# mezza.net
KiCad netlist of a schematic drawn in EAGLE
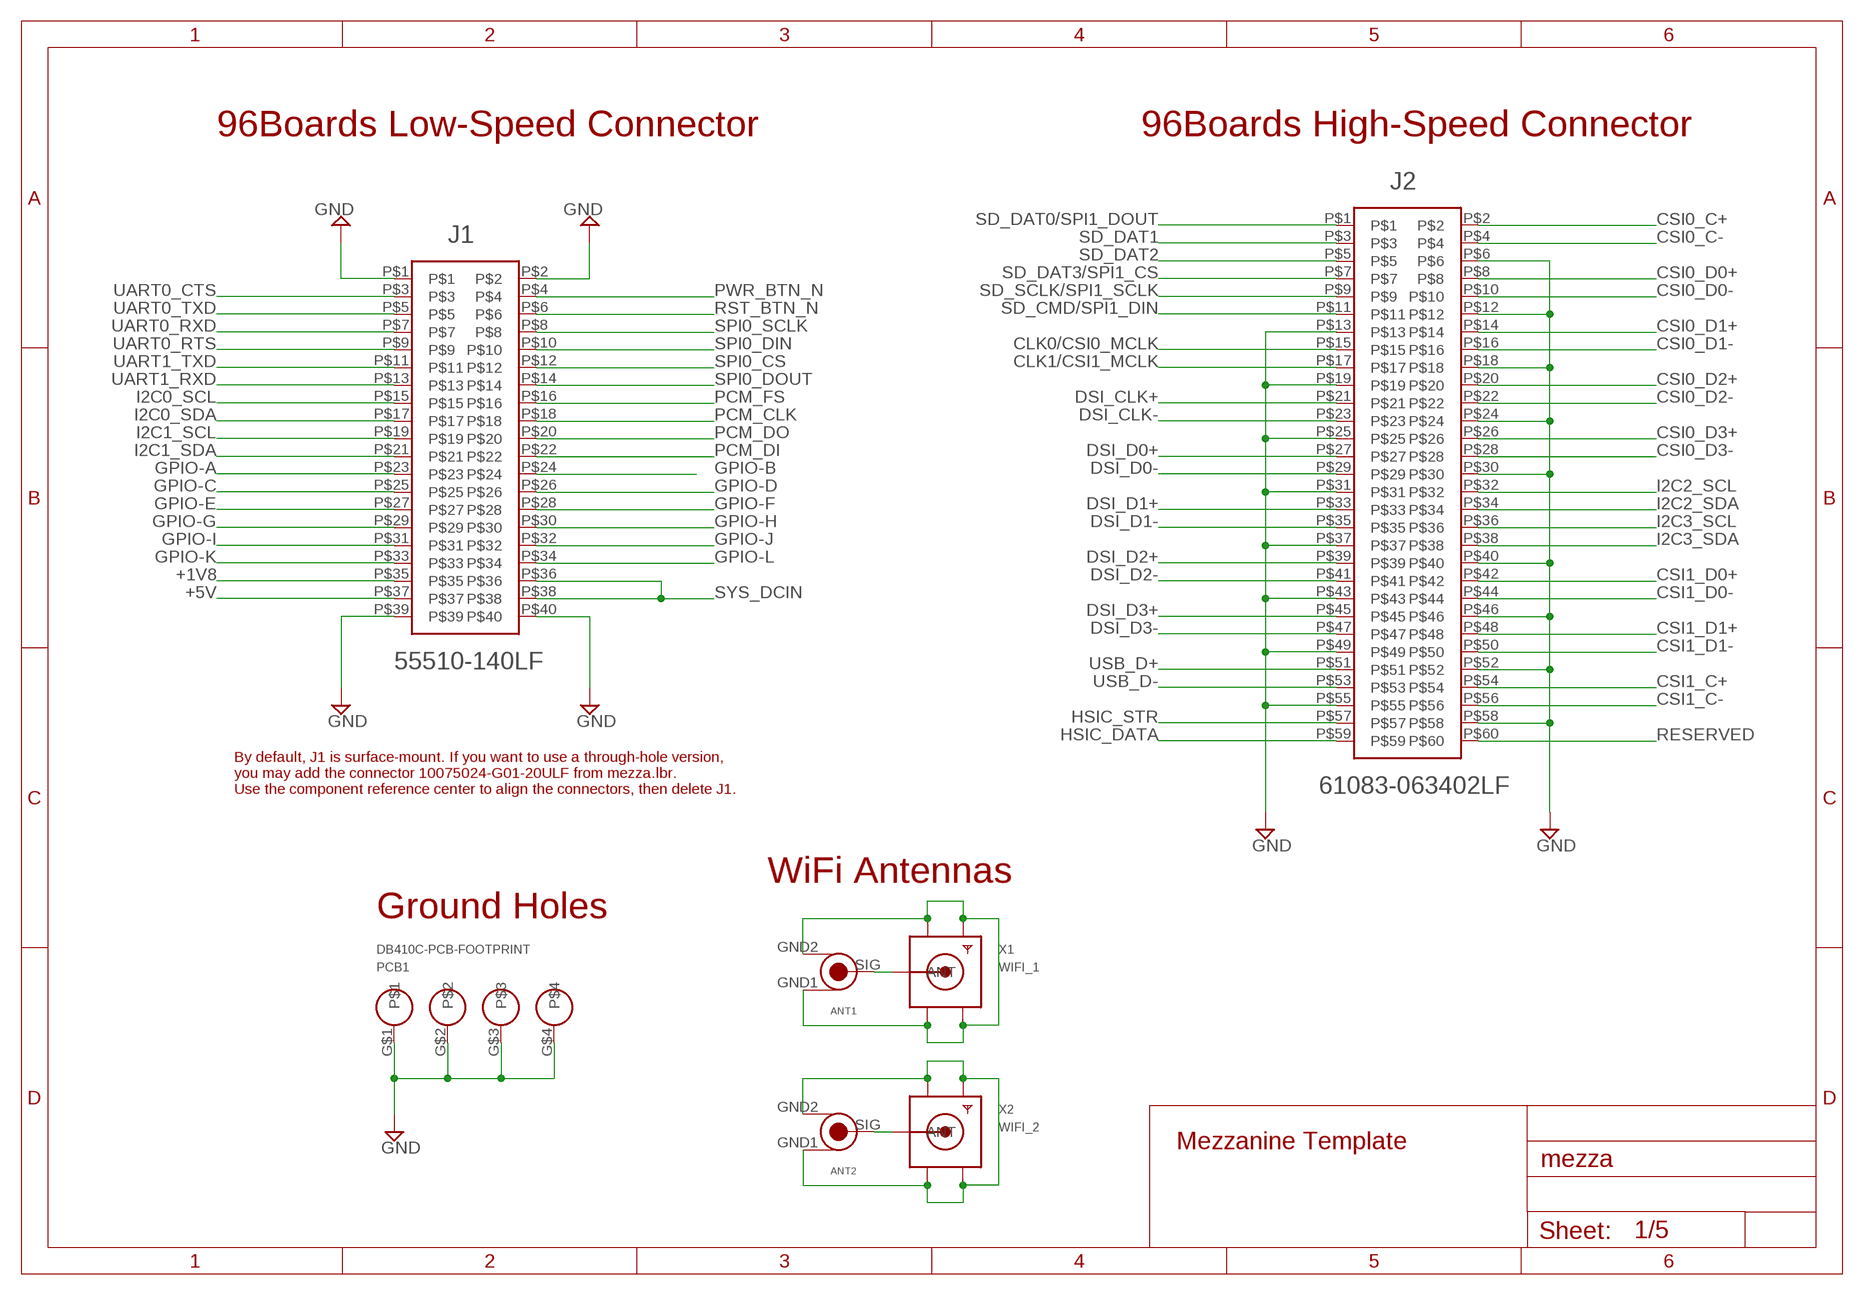
[diagram p0: schematic, sheet 1]
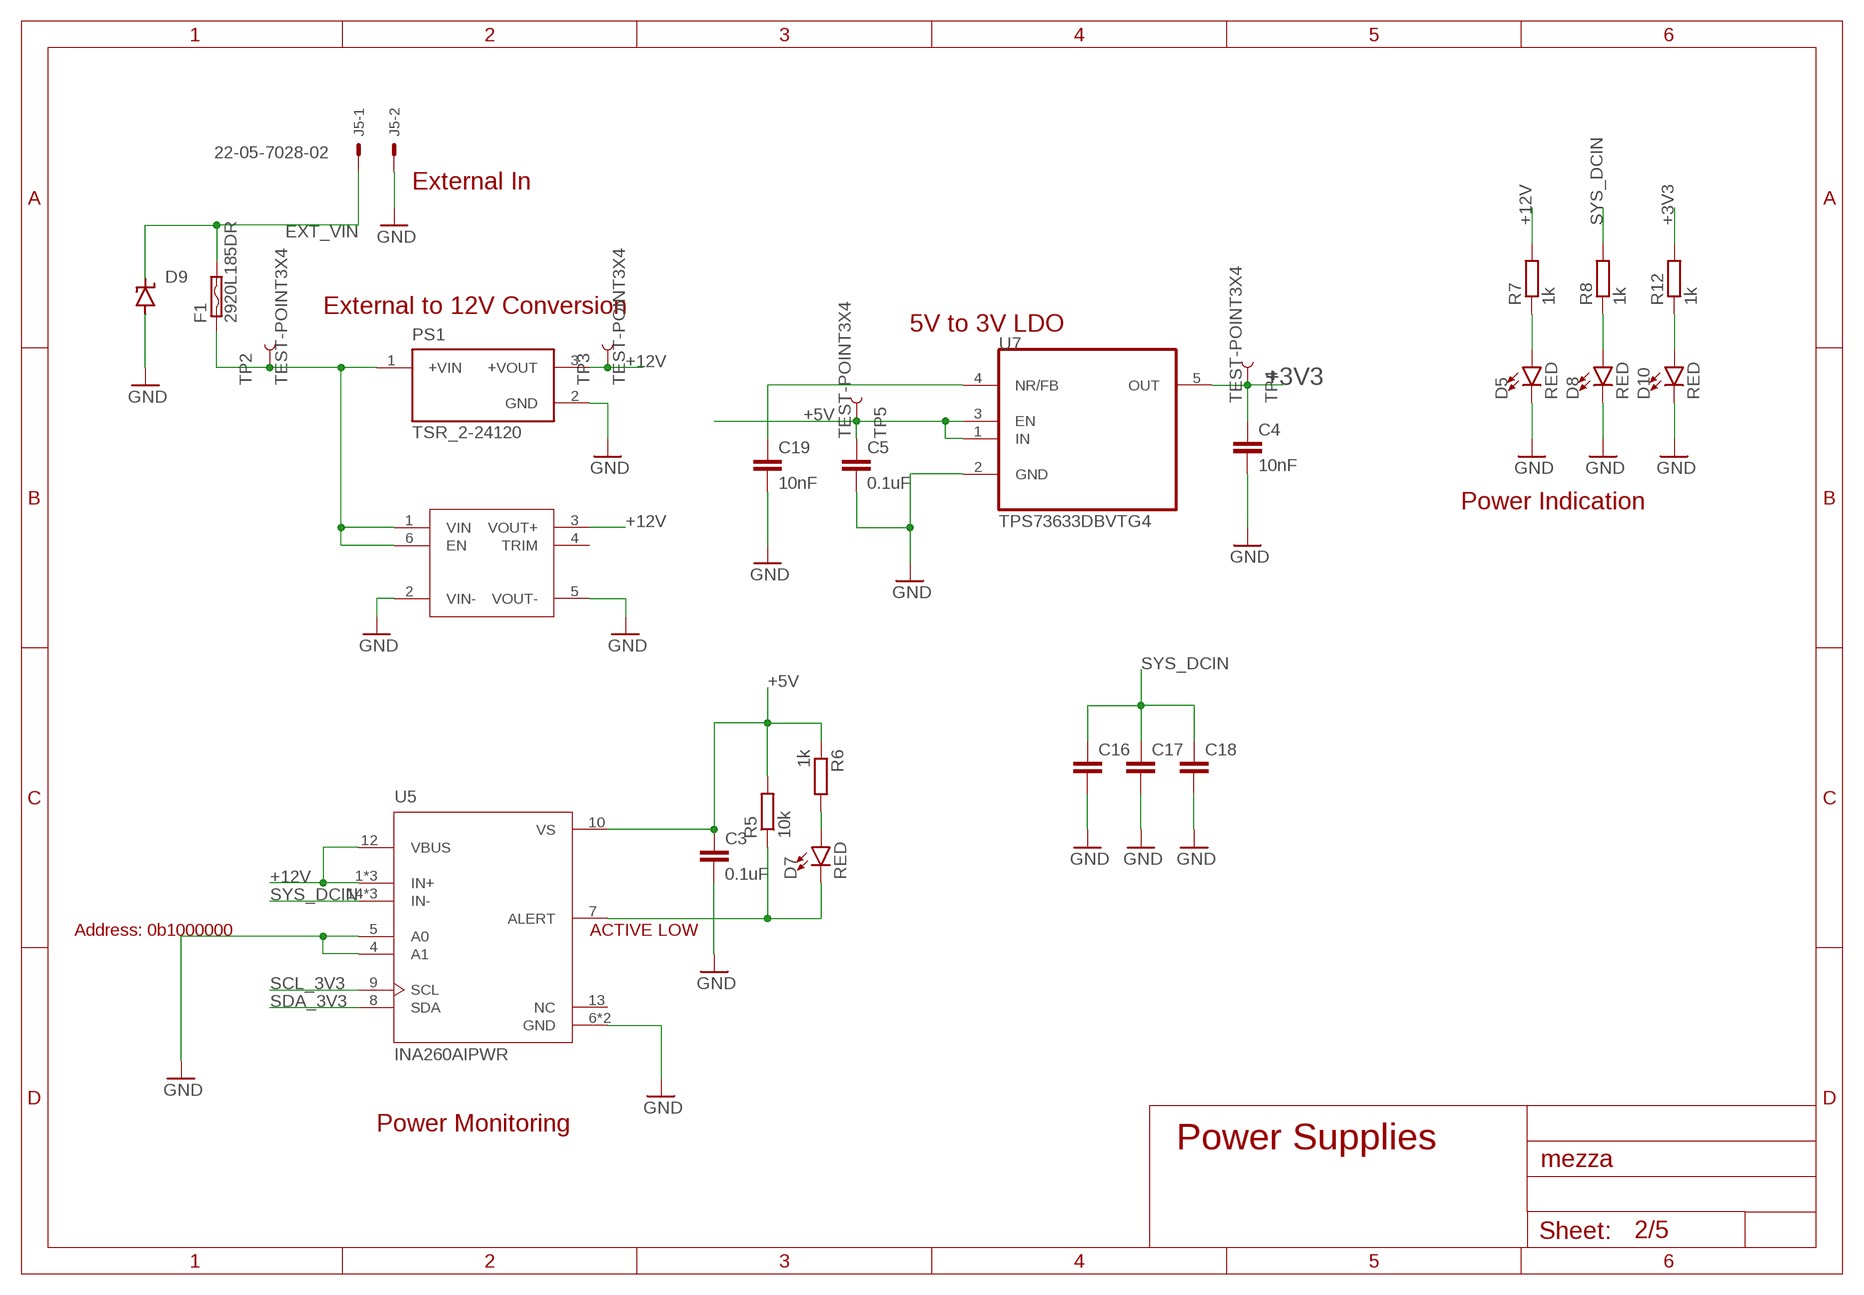
[diagram p1: schematic, sheet 2]
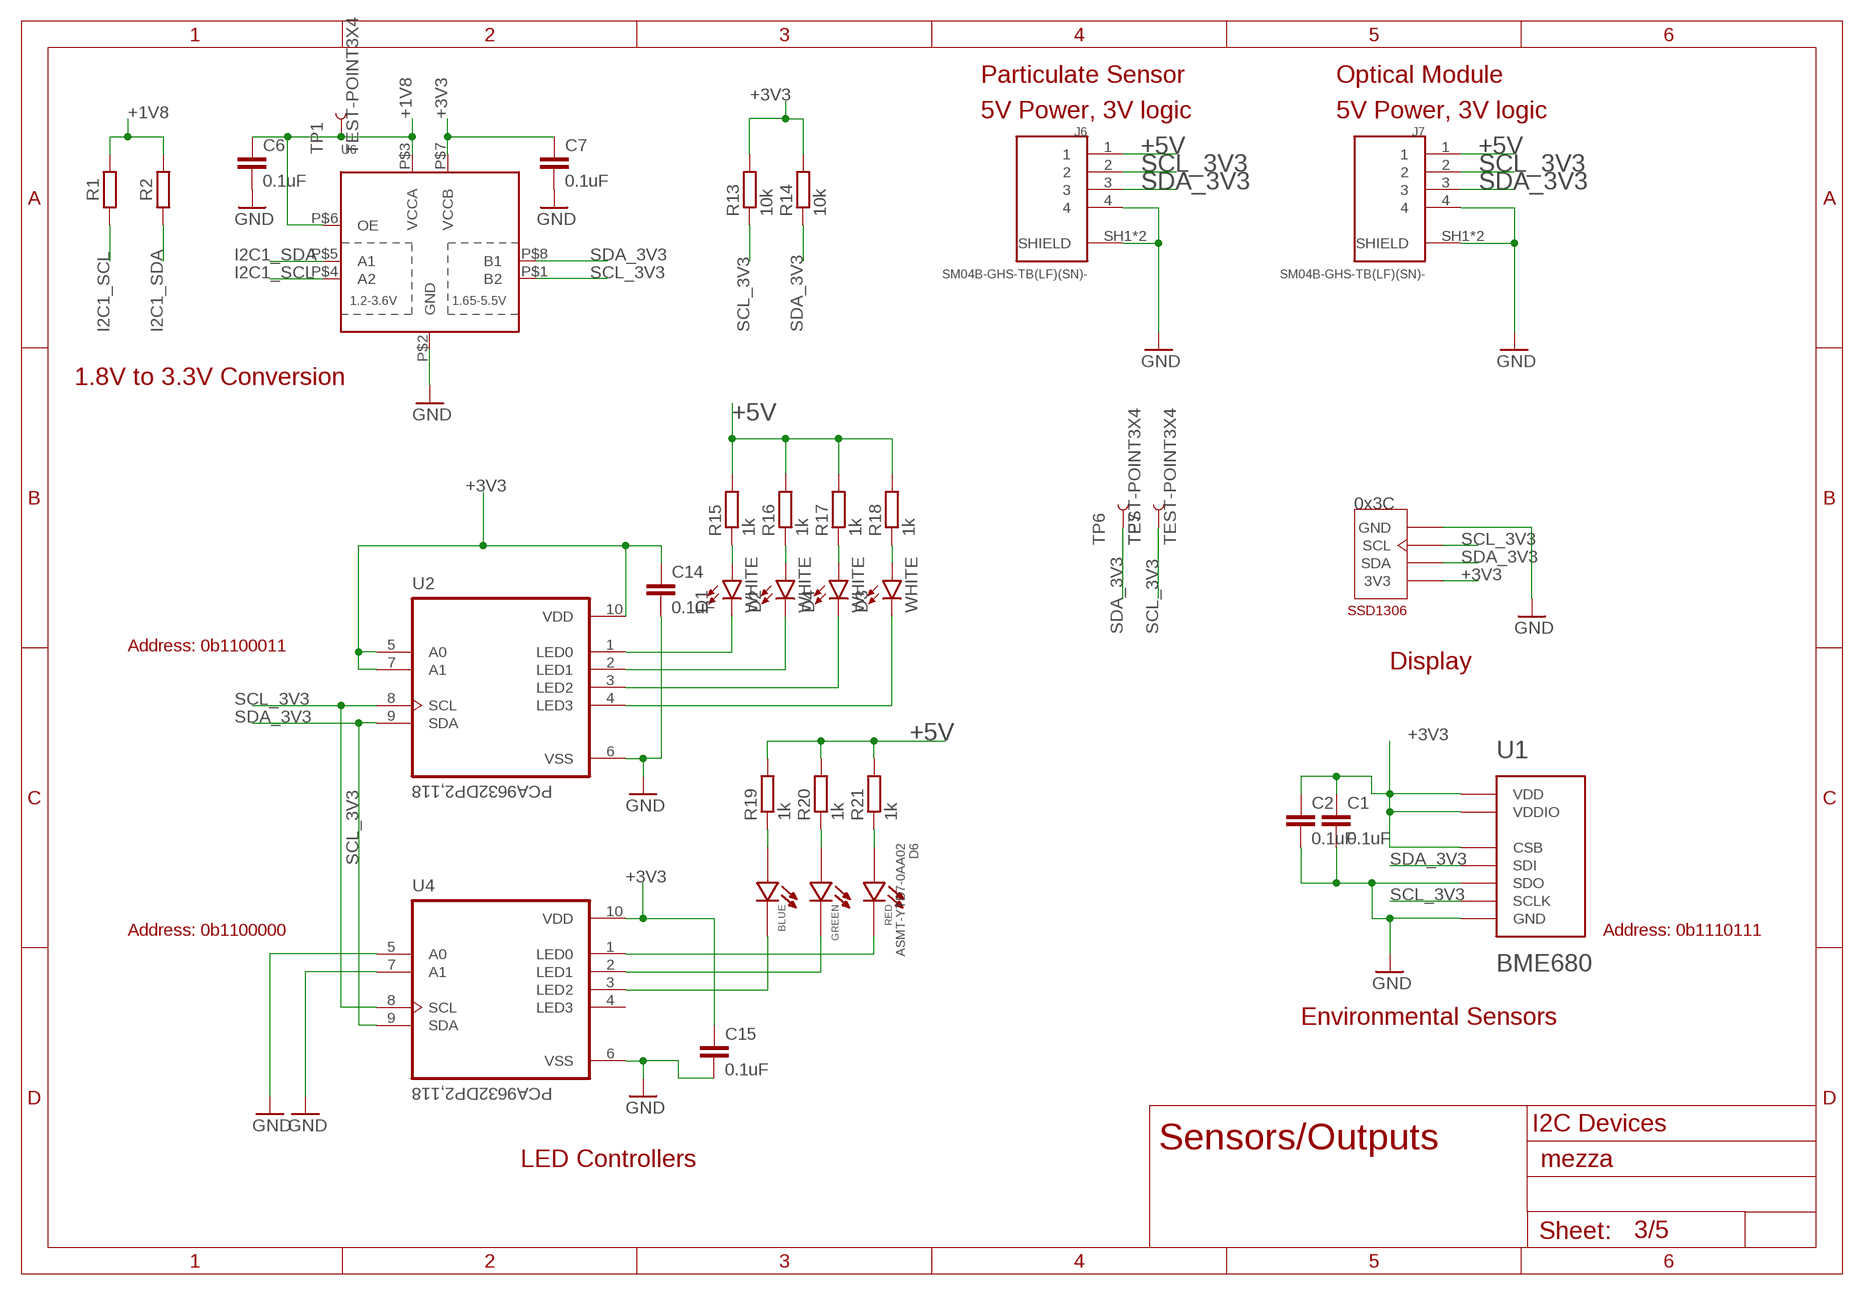
[diagram p2: schematic, sheet 3]
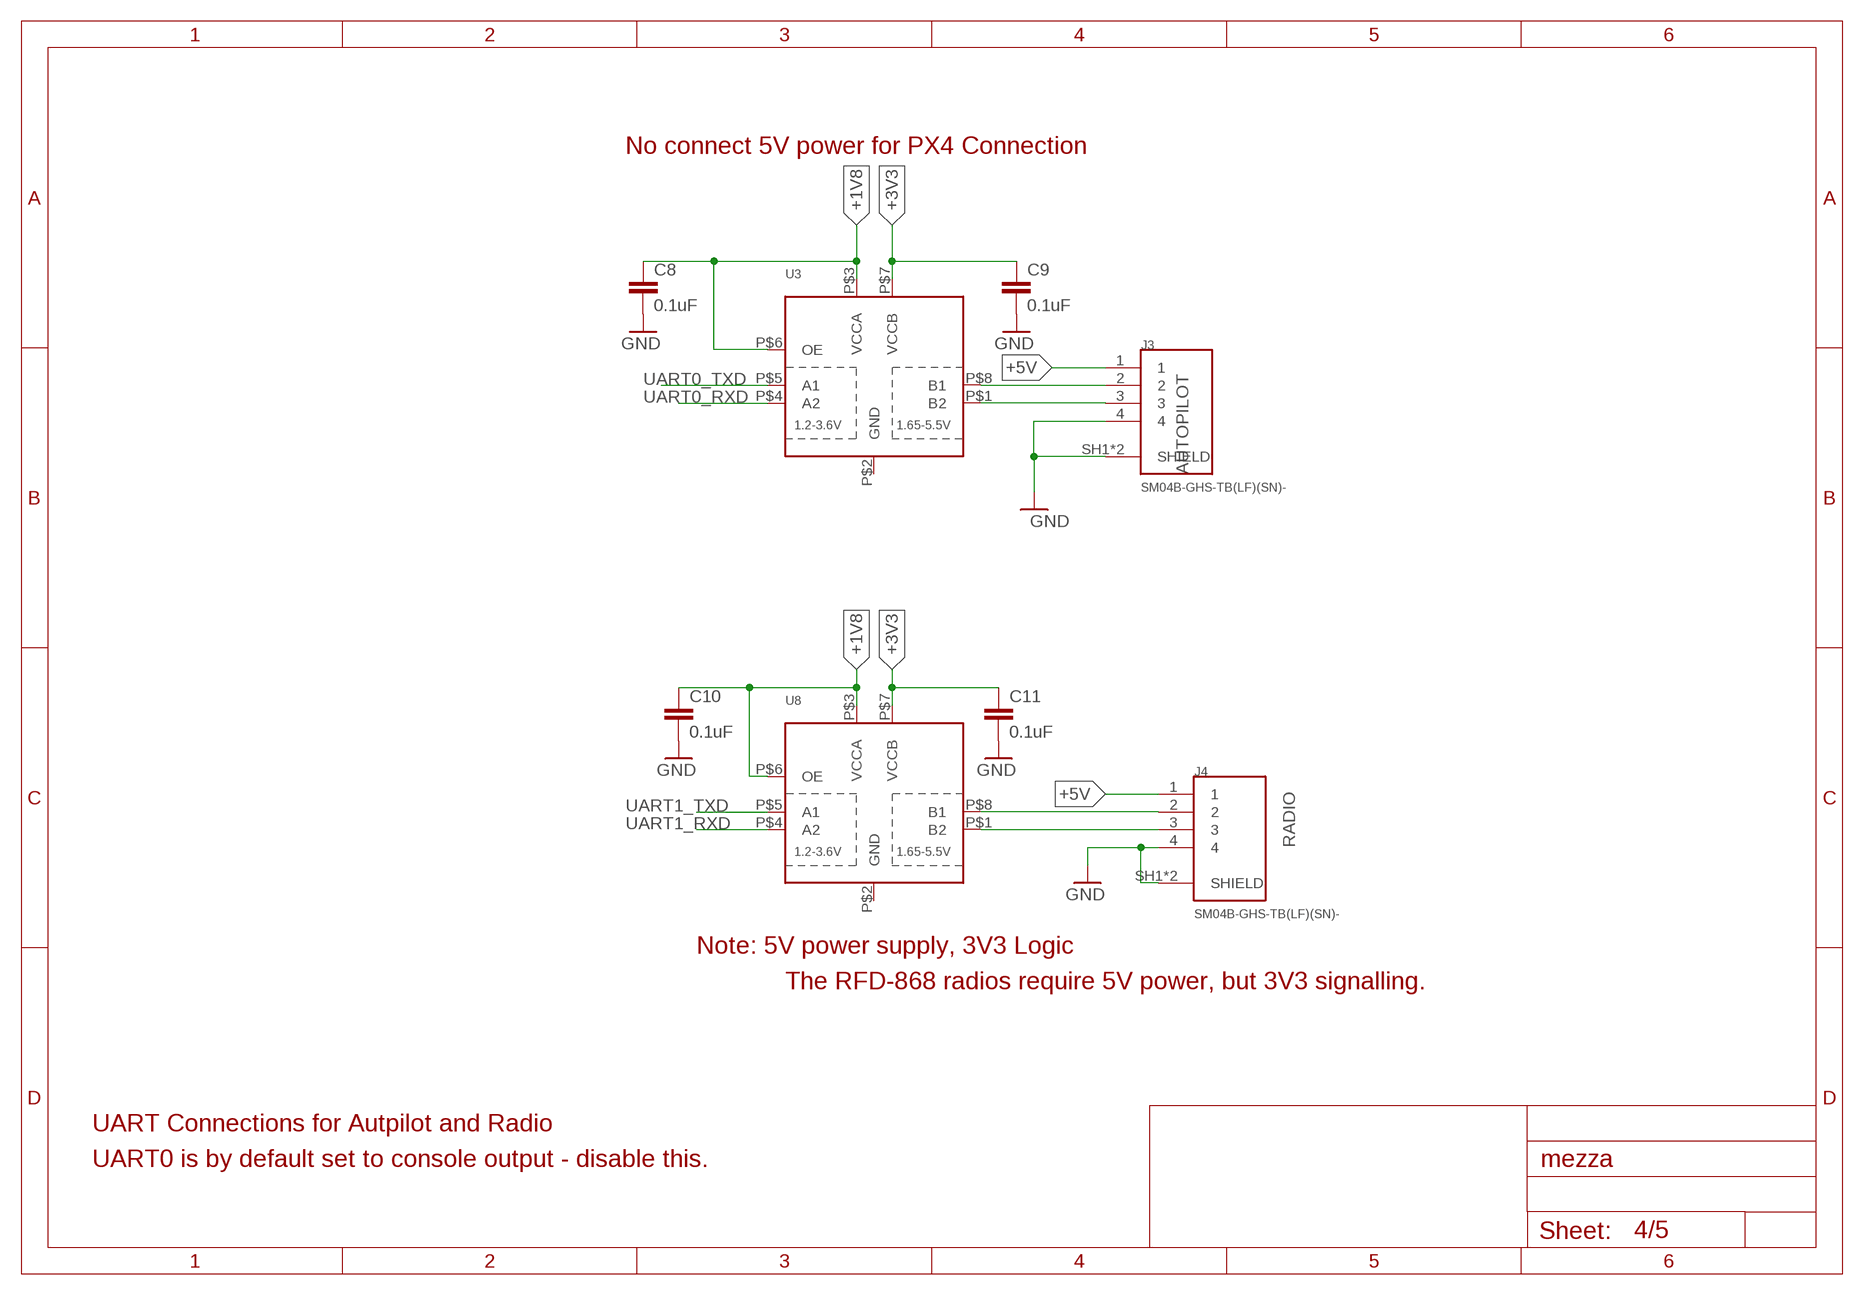
[diagram p3: schematic, sheet 4]
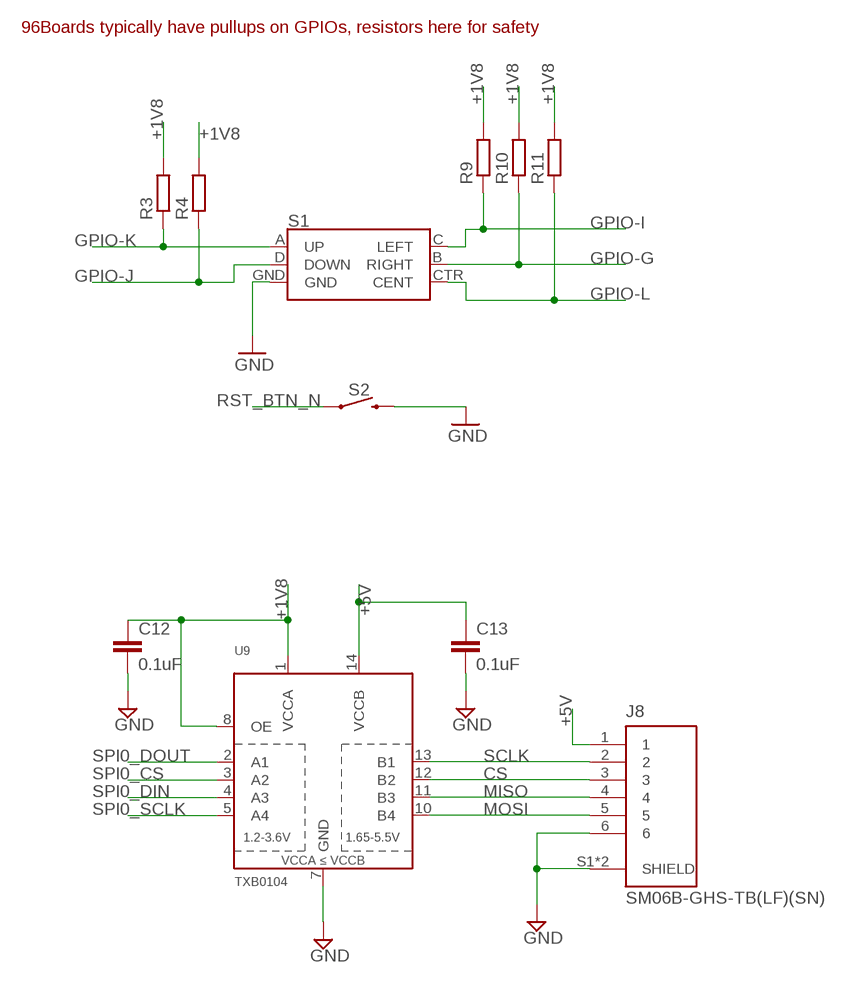
[diagram p4: schematic, sheet 5]

(export (version "E")
  (design (tool "Eeschema 10.0.6"))
  (components
    (comp (ref "ANT1")
      (value "GHI-CONNECTORS_U.FL-R-SMT-1")
      (footprint "eagle-import:GHI-CONNECTORS_U.FL-R-SMT-1")
      (libsource (lib "eagle-import") (part "GHI-CONNECTORS_U.FL-R-SMT-1"))
    )
    (comp (ref "ANT2")
      (value "GHI-CONNECTORS_U.FL-R-SMT-1")
      (footprint "eagle-import:GHI-CONNECTORS_U.FL-R-SMT-1")
      (libsource (lib "eagle-import") (part "GHI-CONNECTORS_U.FL-R-SMT-1"))
    )
    (comp (ref "J1")
      (value "55510-140LF")
      (footprint "eagle-import:55510-140LF")
      (libsource (lib "eagle-import") (part "55510-140LF"))
    )
    (comp (ref "J2")
      (value "61083-063402LF")
      (footprint "eagle-import:61083-063402LF")
      (libsource (lib "eagle-import") (part "61083-063402LF"))
    )
    (comp (ref "PCB1")
      (value "DB410C-PCB-FOOTPRINT")
      (footprint "eagle-import:DRAGONBOARD410C")
      (libsource (lib "eagle-import") (part "DB410C-PCB-FOOTPRINT"))
    )
    (comp (ref "X1")
      (value "WIFI_1")
      (footprint "eagle-import:SMA_EDGELAUNCH")
      (libsource (lib "eagle-import") (part "SMACONNECTOR_EDGE"))
    )
    (comp (ref "X2")
      (value "WIFI_2")
      (footprint "eagle-import:SMA_EDGELAUNCH")
      (libsource (lib "eagle-import") (part "SMACONNECTOR_EDGE"))
    )
    (comp (ref "C12")
      (value "0.1uF")
      (footprint "eagle-import:C0603")
      (libsource (lib "eagle-import") (part "resistor_348_C-EUC0603"))
    )
    (comp (ref "C13")
      (value "0.1uF")
      (footprint "eagle-import:C0603")
      (libsource (lib "eagle-import") (part "resistor_348_C-EUC0603"))
    )
    (comp (ref "J8")
      (value "SM06B-GHS-TB(LF)(SN)")
      (footprint "eagle-import:JST_SM06B-GHS-TB(LF)(SN)")
      (fields (field (name "MF") "JST Sales") (field (name "MP") "SM06B-GHS-TB_LF__SN_"))
      (libsource (lib "eagle-import") (part "SM06B-GHS-TB(LF)(SN)"))
    )
    (comp (ref "R3")
      (value "R-EU_R0603")
      (footprint "eagle-import:R0603")
      (libsource (lib "eagle-import") (part "resistor_348_R-EU_R0603"))
    )
    (comp (ref "R4")
      (value "R-EU_R0603")
      (footprint "eagle-import:R0603")
      (libsource (lib "eagle-import") (part "resistor_348_R-EU_R0603"))
    )
    (comp (ref "R9")
      (value "R-EU_R0603")
      (footprint "eagle-import:R0603")
      (libsource (lib "eagle-import") (part "resistor_348_R-EU_R0603"))
    )
    (comp (ref "R10")
      (value "R-EU_R0603")
      (footprint "eagle-import:R0603")
      (libsource (lib "eagle-import") (part "resistor_348_R-EU_R0603"))
    )
    (comp (ref "R11")
      (value "R-EU_R0603")
      (footprint "eagle-import:R0603")
      (libsource (lib "eagle-import") (part "resistor_348_R-EU_R0603"))
    )
    (comp (ref "S1")
      (value "JOYSTICK_MINI")
      (footprint "eagle-import:JOYSTICK_MINI")
      (libsource (lib "eagle-import") (part "JOYSTICK_MINI"))
    )
    (comp (ref "S2")
      (value "MOMENTARY-SWITCH-SPST-SMD-6.2MM-TALL")
      (footprint "eagle-import:TACTILE_SWITCH_SMD_6.2MM_TALL")
      (libsource (lib "eagle-import") (part "MOMENTARY-SWITCH-SPST-SMD-6.2MM-TALL"))
    )
    (comp (ref "U9")
      (value "TXB0104")
      (footprint "eagle-import:TSSOP14")
      (libsource (lib "eagle-import") (part "TXB0104PWR"))
    )
    (comp (ref "C8")
      (value "0.1uF")
      (footprint "eagle-import:0603")
      (libsource (lib "eagle-import") (part "0.1UF-0603-25V-(+80/-20%)"))
    )
    (comp (ref "C9")
      (value "0.1uF")
      (footprint "eagle-import:0603")
      (libsource (lib "eagle-import") (part "0.1UF-0603-25V-(+80/-20%)"))
    )
    (comp (ref "C10")
      (value "0.1uF")
      (footprint "eagle-import:0603")
      (libsource (lib "eagle-import") (part "0.1UF-0603-25V-(+80/-20%)"))
    )
    (comp (ref "C11")
      (value "0.1uF")
      (footprint "eagle-import:0603")
      (libsource (lib "eagle-import") (part "0.1UF-0603-25V-(+80/-20%)"))
    )
    (comp (ref "J3")
      (value "SM04B-GHS-TB(LF)(SN)-")
      (footprint "eagle-import:JST_SM04B-GHS-TB(LF)(SN)-")
      (fields
        (field (name "DIGI-KEY_PART_NUMBER") "455-1566-1-ND")
        (field (name "MF") "JST Sales")
        (field (name "MP") "SM04B-GHS-TB_LF__SN_-")
      )
      (libsource (lib "eagle-import") (part "SM04B-GHS-TB(LF)(SN)-"))
    )
    (comp (ref "J4")
      (value "SM04B-GHS-TB(LF)(SN)-")
      (footprint "eagle-import:JST_SM04B-GHS-TB(LF)(SN)-")
      (fields
        (field (name "DIGI-KEY_PART_NUMBER") "455-1566-1-ND")
        (field (name "MF") "JST Sales")
        (field (name "MP") "SM04B-GHS-TB_LF__SN_-")
      )
      (libsource (lib "eagle-import") (part "SM04B-GHS-TB(LF)(SN)-"))
    )
    (comp (ref "U3")
      (value "TXS0102")
      (footprint "eagle-import:VFSOP-8")
      (libsource (lib "eagle-import") (part "TXS0102"))
    )
    (comp (ref "U8")
      (value "TXS0102")
      (footprint "eagle-import:VFSOP-8")
      (libsource (lib "eagle-import") (part "TXS0102"))
    )
    (comp (ref "C3")
      (value "0.1uF")
      (footprint "eagle-import:0603")
      (libsource (lib "eagle-import") (part "0.1UF-0603-25V-(+80/-20%)"))
    )
    (comp (ref "C4")
      (value "10nF")
      (footprint "eagle-import:C0603")
      (libsource (lib "eagle-import") (part "C-EUC0603"))
    )
    (comp (ref "C5")
      (value "0.1uF")
      (footprint "eagle-import:C0603")
      (libsource (lib "eagle-import") (part "C-EUC0603"))
    )
    (comp (ref "C16")
      (value "C-EUC1206")
      (footprint "eagle-import:C1206")
      (libsource (lib "eagle-import") (part "resistor_348_C-EUC1206"))
    )
    (comp (ref "C17")
      (value "C-EUC1206")
      (footprint "eagle-import:C1206")
      (libsource (lib "eagle-import") (part "resistor_348_C-EUC1206"))
    )
    (comp (ref "C18")
      (value "C-EUC1206")
      (footprint "eagle-import:C1206")
      (libsource (lib "eagle-import") (part "resistor_348_C-EUC1206"))
    )
    (comp (ref "C19")
      (value "10nF")
      (footprint "eagle-import:C0603")
      (libsource (lib "eagle-import") (part "C-EUC0603"))
    )
    (comp (ref "D5")
      (value "RED")
      (footprint "eagle-import:LED-0603")
      (libsource (lib "eagle-import") (part "LED-RED0603"))
    )
    (comp (ref "D7")
      (value "RED")
      (footprint "eagle-import:LED-0603")
      (libsource (lib "eagle-import") (part "LED-RED0603"))
    )
    (comp (ref "D8")
      (value "RED")
      (footprint "eagle-import:LED-0603")
      (libsource (lib "eagle-import") (part "LED-RED0603"))
    )
    (comp (ref "D9")
      (value "SUPPRESSOR-SMBJ")
      (footprint "eagle-import:SMBJ")
      (libsource (lib "eagle-import") (part "SUPPRESSOR-SMBJ"))
    )
    (comp (ref "D10")
      (value "RED")
      (footprint "eagle-import:LED-0603")
      (libsource (lib "eagle-import") (part "LED-RED0603"))
    )
    (comp (ref "F1")
      (value "2920L185DR")
      (footprint "eagle-import:SMD050F")
      (fields (field (name "MF") "Littelfuse Inc.") (field (name "MP") "2920L200"))
      (libsource (lib "eagle-import") (part "2920L200"))
    )
    (comp (ref "J5")
      (value "22-05-7028-02")
      (footprint "eagle-import:7395-02")
      (fields (field (name "MF") "MOLEX"))
      (libsource (lib "eagle-import") (part "22-?-0205-7028"))
    )
    (comp (ref "PS1")
      (value "TSR_2-24120")
      (footprint "eagle-import:CONV_TSR_2-24120")
      (fields (field (name "MF") "Traco Power") (field (name "MP") "TSR 2-24120"))
      (libsource (lib "eagle-import") (part "TSR_2-24120"))
    )
    (comp (ref "R5")
      (value "10k")
      (footprint "eagle-import:R0603")
      (libsource (lib "eagle-import") (part "R-EU_R0603"))
    )
    (comp (ref "R6")
      (value "1k")
      (footprint "eagle-import:R0603")
      (libsource (lib "eagle-import") (part "R-EU_R0603"))
    )
    (comp (ref "R7")
      (value "1k")
      (footprint "eagle-import:R0603")
      (libsource (lib "eagle-import") (part "R-EU_R0603"))
    )
    (comp (ref "R8")
      (value "1k")
      (footprint "eagle-import:R0603")
      (libsource (lib "eagle-import") (part "R-EU_R0603"))
    )
    (comp (ref "R12")
      (value "1k")
      (footprint "eagle-import:R0603")
      (libsource (lib "eagle-import") (part "R-EU_R0603"))
    )
    (comp (ref "TP2")
      (value "TEST-POINT3X4")
      (footprint "eagle-import:PAD.03X.04")
      (libsource (lib "eagle-import") (part "TEST-POINT3X4"))
    )
    (comp (ref "TP3")
      (value "TEST-POINT3X4")
      (footprint "eagle-import:PAD.03X.04")
      (libsource (lib "eagle-import") (part "TEST-POINT3X4"))
    )
    (comp (ref "TP4")
      (value "TEST-POINT3X4")
      (footprint "eagle-import:PAD.03X.04")
      (libsource (lib "eagle-import") (part "TEST-POINT3X4"))
    )
    (comp (ref "TP5")
      (value "TEST-POINT3X4")
      (footprint "eagle-import:PAD.03X.04")
      (libsource (lib "eagle-import") (part "TEST-POINT3X4"))
    )
    (comp (ref "U$2")
      (value "THN15-2422/3")
      (footprint "eagle-import:TRACOTHN")
      (libsource (lib "eagle-import") (part "THN15-2411"))
    )
    (comp (ref "U5")
      (value "INA260AIPWR")
      (footprint "eagle-import:SOP65P640X120-16N")
      (fields (field (name "MF") "Texas Instruments"))
      (libsource (lib "eagle-import") (part "INA260AIPWR"))
    )
    (comp (ref "U7")
      (value "TPS73633DBVTG4")
      (footprint "eagle-import:SOT23-5")
      (fields (field (name "MF") "Texas Instruments") (field (name "MP") "TPS73633"))
      (libsource (lib "eagle-import") (part "TPS73633DBVTG4"))
    )
    (comp (ref "C1")
      (value "0.1uF")
      (footprint "eagle-import:0603")
      (libsource (lib "eagle-import") (part "0.1UF-0603-25V-(+80/-20%)"))
    )
    (comp (ref "C2")
      (value "0.1uF")
      (footprint "eagle-import:0603")
      (libsource (lib "eagle-import") (part "0.1UF-0603-25V-(+80/-20%)"))
    )
    (comp (ref "C6")
      (value "0.1uF")
      (footprint "eagle-import:0603")
      (libsource (lib "eagle-import") (part "0.1UF-0603-25V-(+80/-20%)"))
    )
    (comp (ref "C7")
      (value "0.1uF")
      (footprint "eagle-import:0603")
      (libsource (lib "eagle-import") (part "0.1UF-0603-25V-(+80/-20%)"))
    )
    (comp (ref "C14")
      (value "0.1uF")
      (footprint "eagle-import:0603")
      (libsource (lib "eagle-import") (part "0.1UF-0603-25V-(+80/-20%)"))
    )
    (comp (ref "C15")
      (value "0.1uF")
      (footprint "eagle-import:0603")
      (libsource (lib "eagle-import") (part "0.1UF-0603-25V-(+80/-20%)"))
    )
    (comp (ref "D1")
      (value "WHITE")
      (footprint "eagle-import:LED-0603")
      (libsource (lib "eagle-import") (part "LED-WHITE0603"))
    )
    (comp (ref "D2")
      (value "WHITE")
      (footprint "eagle-import:LED-0603")
      (libsource (lib "eagle-import") (part "LED-WHITE0603"))
    )
    (comp (ref "D3")
      (value "WHITE")
      (footprint "eagle-import:LED-0603")
      (libsource (lib "eagle-import") (part "LED-WHITE0603"))
    )
    (comp (ref "D4")
      (value "WHITE")
      (footprint "eagle-import:LED-0603")
      (libsource (lib "eagle-import") (part "LED-WHITE0603"))
    )
    (comp (ref "D6")
      (value "ASMT-YTD7-0AA02")
      (footprint "eagle-import:LED_ASMT-YTD7-0AA02")
      (fields (field (name "DIGI-KEY_PART_NUMBER") "516-3219-1-ND") (field (name "MF") "Broadcom Limited"))
      (libsource (lib "eagle-import") (part "ASMT-YTD7-0AA02"))
    )
    (comp (ref "J6")
      (value "SM04B-GHS-TB(LF)(SN)-")
      (footprint "eagle-import:JST_SM04B-GHS-TB(LF)(SN)-")
      (fields
        (field (name "DIGI-KEY_PART_NUMBER") "455-1566-1-ND")
        (field (name "MF") "JST Sales")
        (field (name "MP") "SM04B-GHS-TB_LF__SN_-")
      )
      (libsource (lib "eagle-import") (part "SM04B-GHS-TB(LF)(SN)-"))
    )
    (comp (ref "J7")
      (value "SM04B-GHS-TB(LF)(SN)-")
      (footprint "eagle-import:JST_SM04B-GHS-TB(LF)(SN)-")
      (fields
        (field (name "DIGI-KEY_PART_NUMBER") "455-1566-1-ND")
        (field (name "MF") "JST Sales")
        (field (name "MP") "SM04B-GHS-TB_LF__SN_-")
      )
      (libsource (lib "eagle-import") (part "SM04B-GHS-TB(LF)(SN)-"))
    )
    (comp (ref "R1")
      (value "10k")
      (footprint "eagle-import:R0603")
      (libsource (lib "eagle-import") (part "R-EU_R0603"))
    )
    (comp (ref "R2")
      (value "10k")
      (footprint "eagle-import:R0603")
      (libsource (lib "eagle-import") (part "R-EU_R0603"))
    )
    (comp (ref "R13")
      (value "10k")
      (footprint "eagle-import:R0603")
      (libsource (lib "eagle-import") (part "R-EU_R0603"))
    )
    (comp (ref "R14")
      (value "10k")
      (footprint "eagle-import:R0603")
      (libsource (lib "eagle-import") (part "R-EU_R0603"))
    )
    (comp (ref "R15")
      (value "1k")
      (footprint "eagle-import:R0603")
      (libsource (lib "eagle-import") (part "R-EU_R0603"))
    )
    (comp (ref "R16")
      (value "1k")
      (footprint "eagle-import:R0603")
      (libsource (lib "eagle-import") (part "R-EU_R0603"))
    )
    (comp (ref "R17")
      (value "1k")
      (footprint "eagle-import:R0603")
      (libsource (lib "eagle-import") (part "R-EU_R0603"))
    )
    (comp (ref "R18")
      (value "1k")
      (footprint "eagle-import:R0603")
      (libsource (lib "eagle-import") (part "R-EU_R0603"))
    )
    (comp (ref "R19")
      (value "1k")
      (footprint "eagle-import:R0603")
      (libsource (lib "eagle-import") (part "R-EU_R0603"))
    )
    (comp (ref "R20")
      (value "1k")
      (footprint "eagle-import:R0603")
      (libsource (lib "eagle-import") (part "R-EU_R0603"))
    )
    (comp (ref "R21")
      (value "1k")
      (footprint "eagle-import:R0603")
      (libsource (lib "eagle-import") (part "R-EU_R0603"))
    )
    (comp (ref "TP1")
      (value "TEST-POINT3X4")
      (footprint "eagle-import:PAD.03X.04")
      (libsource (lib "eagle-import") (part "TEST-POINT3X4"))
    )
    (comp (ref "TP6")
      (value "TEST-POINT3X4")
      (footprint "eagle-import:PAD.03X.04")
      (libsource (lib "eagle-import") (part "TEST-POINT3X4"))
    )
    (comp (ref "TP7")
      (value "TEST-POINT3X4")
      (footprint "eagle-import:PAD.03X.04")
      (libsource (lib "eagle-import") (part "TEST-POINT3X4"))
    )
    (comp (ref "U$1")
      (value "SSD1306")
      (footprint "eagle-import:128_32_OLED")
      (libsource (lib "eagle-import") (part "SSD1306"))
    )
    (comp (ref "U1")
      (value "BME680")
      (footprint "eagle-import:LGA-8")
      (libsource (lib "eagle-import") (part "BME680"))
    )
    (comp (ref "U2")
      (value "PCA9632DP2,118")
      (footprint "eagle-import:SOP50P490X110-10N")
      (fields (field (name "MF") "NXP USA"))
      (libsource (lib "eagle-import") (part "PCA9632DP2,118"))
    )
    (comp (ref "U4")
      (value "PCA9632DP2,118")
      (footprint "eagle-import:SOP50P490X110-10N")
      (fields (field (name "MF") "NXP USA"))
      (libsource (lib "eagle-import") (part "PCA9632DP2,118"))
    )
    (comp (ref "U6")
      (value "TXS0102")
      (footprint "eagle-import:VFSOP-8")
      (libsource (lib "eagle-import") (part "TXS0102"))
    )
  )
  (nets
    (net (code "1") (name "+1V8") (class "Default")
      (node (ref "C10") (pin "1") (pinfunction "1_1") (pintype "passive"))
      (node (ref "C12") (pin "1") (pinfunction "1_1") (pintype "passive"))
      (node (ref "C6") (pin "1") (pinfunction "1_1") (pintype "passive"))
      (node (ref "C8") (pin "1") (pinfunction "1_1") (pintype "passive"))
      (node (ref "J1") (pin "P$35") (pinfunction "P$35_P$35") (pintype "bidirectional"))
      (node (ref "R1") (pin "2") (pinfunction "2_2") (pintype "passive"))
      (node (ref "R10") (pin "2") (pinfunction "2_2") (pintype "passive"))
      (node (ref "R11") (pin "2") (pinfunction "2_2") (pintype "passive"))
      (node (ref "R2") (pin "2") (pinfunction "2_2") (pintype "passive"))
      (node (ref "R3") (pin "2") (pinfunction "2_2") (pintype "passive"))
      (node (ref "R4") (pin "2") (pinfunction "2_2") (pintype "passive"))
      (node (ref "R9") (pin "2") (pinfunction "2_2") (pintype "passive"))
      (node (ref "TP1") (pin "P$1") (pinfunction "1_P$1") (pintype "bidirectional"))
      (node (ref "U3") (pin "P$3") (pinfunction "VCCA_P$3") (pintype "bidirectional"))
      (node (ref "U3") (pin "P$6") (pinfunction "OE_P$6") (pintype "bidirectional"))
      (node (ref "U6") (pin "P$3") (pinfunction "VCCA_P$3") (pintype "bidirectional"))
      (node (ref "U6") (pin "P$6") (pinfunction "OE_P$6") (pintype "bidirectional"))
      (node (ref "U8") (pin "P$3") (pinfunction "VCCA_P$3") (pintype "bidirectional"))
      (node (ref "U8") (pin "P$6") (pinfunction "OE_P$6") (pintype "bidirectional"))
      (node (ref "U9") (pin "1") (pinfunction "VCCA_1") (pintype "bidirectional"))
      (node (ref "U9") (pin "8") (pinfunction "OE_8") (pintype "bidirectional"))
    )
    (net (code "2") (name "+3V3") (class "Default")
      (node (ref "C1") (pin "1") (pinfunction "1_1") (pintype "passive"))
      (node (ref "C11") (pin "1") (pinfunction "1_1") (pintype "passive"))
      (node (ref "C14") (pin "1") (pinfunction "1_1") (pintype "passive"))
      (node (ref "C15") (pin "1") (pinfunction "1_1") (pintype "passive"))
      (node (ref "C2") (pin "1") (pinfunction "1_1") (pintype "passive"))
      (node (ref "C4") (pin "1") (pinfunction "1_1") (pintype "passive"))
      (node (ref "C7") (pin "1") (pinfunction "1_1") (pintype "passive"))
      (node (ref "C9") (pin "1") (pinfunction "1_1") (pintype "passive"))
      (node (ref "R12") (pin "2") (pinfunction "2_2") (pintype "passive"))
      (node (ref "R13") (pin "2") (pinfunction "2_2") (pintype "passive"))
      (node (ref "R14") (pin "2") (pinfunction "2_2") (pintype "passive"))
      (node (ref "TP4") (pin "P$1") (pinfunction "1_P$1") (pintype "bidirectional"))
      (node (ref "U$1") (pin "3V3") (pinfunction "3V3_3V3") (pintype "power_in"))
      (node (ref "U1") (pin "2") (pinfunction "CSB_2") (pintype "bidirectional"))
      (node (ref "U1") (pin "6") (pinfunction "VDDIO_6") (pintype "power_in"))
      (node (ref "U1") (pin "8") (pinfunction "VDD_8") (pintype "power_in"))
      (node (ref "U2") (pin "10") (pinfunction "VDD_10") (pintype "power_in"))
      (node (ref "U2") (pin "5") (pinfunction "A0_5") (pintype "input"))
      (node (ref "U2") (pin "7") (pinfunction "A1_7") (pintype "input"))
      (node (ref "U3") (pin "P$7") (pinfunction "VCCB_P$7") (pintype "bidirectional"))
      (node (ref "U4") (pin "10") (pinfunction "VDD_10") (pintype "power_in"))
      (node (ref "U6") (pin "P$7") (pinfunction "VCCB_P$7") (pintype "bidirectional"))
      (node (ref "U7") (pin "5") (pinfunction "OUT_5") (pintype "output"))
      (node (ref "U8") (pin "P$7") (pinfunction "VCCB_P$7") (pintype "bidirectional"))
    )
    (net (code "3") (name "+5V") (class "Default")
      (node (ref "C13") (pin "1") (pinfunction "1_1") (pintype "passive"))
      (node (ref "C3") (pin "1") (pinfunction "1_1") (pintype "passive"))
      (node (ref "C5") (pin "1") (pinfunction "1_1") (pintype "passive"))
      (node (ref "J1") (pin "P$37") (pinfunction "P$37_P$37") (pintype "bidirectional"))
      (node (ref "J3") (pin "1") (pinfunction "1_1") (pintype "passive"))
      (node (ref "J4") (pin "1") (pinfunction "1_1") (pintype "passive"))
      (node (ref "J6") (pin "1") (pinfunction "1_1") (pintype "passive"))
      (node (ref "J7") (pin "1") (pinfunction "1_1") (pintype "passive"))
      (node (ref "J8") (pin "1") (pinfunction "1_1") (pintype "passive"))
      (node (ref "R15") (pin "2") (pinfunction "2_2") (pintype "passive"))
      (node (ref "R16") (pin "2") (pinfunction "2_2") (pintype "passive"))
      (node (ref "R17") (pin "2") (pinfunction "2_2") (pintype "passive"))
      (node (ref "R18") (pin "2") (pinfunction "2_2") (pintype "passive"))
      (node (ref "R19") (pin "2") (pinfunction "2_2") (pintype "passive"))
      (node (ref "R20") (pin "2") (pinfunction "2_2") (pintype "passive"))
      (node (ref "R21") (pin "2") (pinfunction "2_2") (pintype "passive"))
      (node (ref "R5") (pin "2") (pinfunction "2_2") (pintype "passive"))
      (node (ref "R6") (pin "1") (pinfunction "1_1") (pintype "passive"))
      (node (ref "TP5") (pin "P$1") (pinfunction "1_P$1") (pintype "bidirectional"))
      (node (ref "U5") (pin "10") (pinfunction "VS_10") (pintype "power_in"))
      (node (ref "U7") (pin "1") (pinfunction "IN_1") (pintype "input"))
      (node (ref "U7") (pin "3") (pinfunction "EN_3") (pintype "input"))
      (node (ref "U9") (pin "14") (pinfunction "VCCB_14") (pintype "bidirectional"))
    )
    (net (code "4") (name "+12V") (class "Default")
      (node (ref "PS1") (pin "3") (pinfunction "+VOUT_3") (pintype "output"))
      (node (ref "R7") (pin "2") (pinfunction "2_2") (pintype "passive"))
      (node (ref "TP3") (pin "P$1") (pinfunction "1_P$1") (pintype "bidirectional"))
      (node (ref "U$2") (pin "3") (pinfunction "VOUT+_3") (pintype "bidirectional"))
      (node (ref "U5") (pin "1") (pinfunction "IN+_1") (pintype "input"))
      (node (ref "U5") (pin "12") (pinfunction "VBUS_12") (pintype "input"))
      (node (ref "U5") (pin "2") (pinfunction "IN+_2") (pintype "input"))
      (node (ref "U5") (pin "3") (pinfunction "IN+_3") (pintype "input"))
    )
    (net (code "5") (name "CLK0{slash}CSI0_MCLK") (class "Default")
      (node (ref "J2") (pin "P$15") (pinfunction "P$15_P$15") (pintype "bidirectional"))
    )
    (net (code "6") (name "CLK1{slash}CSI1_MCLK") (class "Default")
      (node (ref "J2") (pin "P$17") (pinfunction "P$17_P$17") (pintype "bidirectional"))
    )
    (net (code "7") (name "CS") (class "Default")
      (node (ref "J8") (pin "3") (pinfunction "3_3") (pintype "passive"))
      (node (ref "U9") (pin "12") (pinfunction "B2_12") (pintype "bidirectional"))
    )
    (net (code "8") (name "CSI0_C+") (class "Default")
      (node (ref "J2") (pin "P$2") (pinfunction "P$2_P$2") (pintype "bidirectional"))
    )
    (net (code "9") (name "CSI0_C-") (class "Default")
      (node (ref "J2") (pin "P$4") (pinfunction "P$4_P$4") (pintype "bidirectional"))
    )
    (net (code "10") (name "CSI0_D0+") (class "Default")
      (node (ref "J2") (pin "P$8") (pinfunction "P$8_P$8") (pintype "bidirectional"))
    )
    (net (code "11") (name "CSI0_D0-") (class "Default")
      (node (ref "J2") (pin "P$10") (pinfunction "P$10_P$10") (pintype "bidirectional"))
    )
    (net (code "12") (name "CSI0_D1+") (class "Default")
      (node (ref "J2") (pin "P$14") (pinfunction "P$14_P$14") (pintype "bidirectional"))
    )
    (net (code "13") (name "CSI0_D1-") (class "Default")
      (node (ref "J2") (pin "P$16") (pinfunction "P$16_P$16") (pintype "bidirectional"))
    )
    (net (code "14") (name "CSI0_D2+") (class "Default")
      (node (ref "J2") (pin "P$20") (pinfunction "P$20_P$20") (pintype "bidirectional"))
    )
    (net (code "15") (name "CSI0_D2-") (class "Default")
      (node (ref "J2") (pin "P$22") (pinfunction "P$22_P$22") (pintype "bidirectional"))
    )
    (net (code "16") (name "CSI0_D3+") (class "Default")
      (node (ref "J2") (pin "P$26") (pinfunction "P$26_P$26") (pintype "bidirectional"))
    )
    (net (code "17") (name "CSI0_D3-") (class "Default")
      (node (ref "J2") (pin "P$28") (pinfunction "P$28_P$28") (pintype "bidirectional"))
    )
    (net (code "18") (name "CSI1_C+") (class "Default")
      (node (ref "J2") (pin "P$54") (pinfunction "P$54_P$54") (pintype "bidirectional"))
    )
    (net (code "19") (name "CSI1_C-") (class "Default")
      (node (ref "J2") (pin "P$56") (pinfunction "P$56_P$56") (pintype "bidirectional"))
    )
    (net (code "20") (name "CSI1_D0+") (class "Default")
      (node (ref "J2") (pin "P$42") (pinfunction "P$42_P$42") (pintype "bidirectional"))
    )
    (net (code "21") (name "CSI1_D0-") (class "Default")
      (node (ref "J2") (pin "P$44") (pinfunction "P$44_P$44") (pintype "bidirectional"))
    )
    (net (code "22") (name "CSI1_D1+") (class "Default")
      (node (ref "J2") (pin "P$48") (pinfunction "P$48_P$48") (pintype "bidirectional"))
    )
    (net (code "23") (name "CSI1_D1-") (class "Default")
      (node (ref "J2") (pin "P$50") (pinfunction "P$50_P$50") (pintype "bidirectional"))
    )
    (net (code "24") (name "DSI_CLK+") (class "Default")
      (node (ref "J2") (pin "P$21") (pinfunction "P$21_P$21") (pintype "bidirectional"))
    )
    (net (code "25") (name "DSI_CLK-") (class "Default")
      (node (ref "J2") (pin "P$23") (pinfunction "P$23_P$23") (pintype "bidirectional"))
    )
    (net (code "26") (name "DSI_D0+") (class "Default")
      (node (ref "J2") (pin "P$27") (pinfunction "P$27_P$27") (pintype "bidirectional"))
    )
    (net (code "27") (name "DSI_D0-") (class "Default")
      (node (ref "J2") (pin "P$29") (pinfunction "P$29_P$29") (pintype "bidirectional"))
    )
    (net (code "28") (name "DSI_D1+") (class "Default")
      (node (ref "J2") (pin "P$33") (pinfunction "P$33_P$33") (pintype "bidirectional"))
    )
    (net (code "29") (name "DSI_D1-") (class "Default")
      (node (ref "J2") (pin "P$35") (pinfunction "P$35_P$35") (pintype "bidirectional"))
    )
    (net (code "30") (name "DSI_D2+") (class "Default")
      (node (ref "J2") (pin "P$39") (pinfunction "P$39_P$39") (pintype "bidirectional"))
    )
    (net (code "31") (name "DSI_D2-") (class "Default")
      (node (ref "J2") (pin "P$41") (pinfunction "P$41_P$41") (pintype "bidirectional"))
    )
    (net (code "32") (name "DSI_D3+") (class "Default")
      (node (ref "J2") (pin "P$45") (pinfunction "P$45_P$45") (pintype "bidirectional"))
    )
    (net (code "33") (name "DSI_D3-") (class "Default")
      (node (ref "J2") (pin "P$47") (pinfunction "P$47_P$47") (pintype "bidirectional"))
    )
    (net (code "34") (name "EXT_VIN") (class "Default")
      (node (ref "D9") (pin "C") (pinfunction "C_C") (pintype "passive"))
      (node (ref "F1") (pin "2") (pinfunction "2_2") (pintype "passive"))
      (node (ref "J5") (pin "1") (pinfunction "S_1") (pintype "passive"))
    )
    (net (code "35") (name "GND") (class "Default")
      (node (ref "C1") (pin "2") (pinfunction "2_2") (pintype "passive"))
      (node (ref "C10") (pin "2") (pinfunction "2_2") (pintype "passive"))
      (node (ref "C11") (pin "2") (pinfunction "2_2") (pintype "passive"))
      (node (ref "C12") (pin "2") (pinfunction "2_2") (pintype "passive"))
      (node (ref "C13") (pin "2") (pinfunction "2_2") (pintype "passive"))
      (node (ref "C14") (pin "2") (pinfunction "2_2") (pintype "passive"))
      (node (ref "C15") (pin "2") (pinfunction "2_2") (pintype "passive"))
      (node (ref "C16") (pin "2") (pinfunction "2_2") (pintype "passive"))
      (node (ref "C17") (pin "2") (pinfunction "2_2") (pintype "passive"))
      (node (ref "C18") (pin "2") (pinfunction "2_2") (pintype "passive"))
      (node (ref "C19") (pin "2") (pinfunction "2_2") (pintype "passive"))
      (node (ref "C2") (pin "2") (pinfunction "2_2") (pintype "passive"))
      (node (ref "C3") (pin "2") (pinfunction "2_2") (pintype "passive"))
      (node (ref "C4") (pin "2") (pinfunction "2_2") (pintype "passive"))
      (node (ref "C5") (pin "2") (pinfunction "2_2") (pintype "passive"))
      (node (ref "C6") (pin "2") (pinfunction "2_2") (pintype "passive"))
      (node (ref "C7") (pin "2") (pinfunction "2_2") (pintype "passive"))
      (node (ref "C8") (pin "2") (pinfunction "2_2") (pintype "passive"))
      (node (ref "C9") (pin "2") (pinfunction "2_2") (pintype "passive"))
      (node (ref "D10") (pin "C") (pinfunction "C_C") (pintype "passive"))
      (node (ref "D5") (pin "C") (pinfunction "C_C") (pintype "passive"))
      (node (ref "D8") (pin "C") (pinfunction "C_C") (pintype "passive"))
      (node (ref "D9") (pin "A") (pinfunction "A_A") (pintype "passive"))
      (node (ref "J1") (pin "P$1") (pinfunction "P$1_P$1") (pintype "bidirectional"))
      (node (ref "J1") (pin "P$2") (pinfunction "P$2_P$2") (pintype "bidirectional"))
      (node (ref "J1") (pin "P$39") (pinfunction "P$39_P$39") (pintype "bidirectional"))
      (node (ref "J1") (pin "P$40") (pinfunction "P$40_P$40") (pintype "bidirectional"))
      (node (ref "J2") (pin "P$12") (pinfunction "P$12_P$12") (pintype "bidirectional"))
      (node (ref "J2") (pin "P$13") (pinfunction "P$13_P$13") (pintype "bidirectional"))
      (node (ref "J2") (pin "P$18") (pinfunction "P$18_P$18") (pintype "bidirectional"))
      (node (ref "J2") (pin "P$19") (pinfunction "P$19_P$19") (pintype "bidirectional"))
      (node (ref "J2") (pin "P$24") (pinfunction "P$24_P$24") (pintype "bidirectional"))
      (node (ref "J2") (pin "P$25") (pinfunction "P$25_P$25") (pintype "bidirectional"))
      (node (ref "J2") (pin "P$30") (pinfunction "P$30_P$30") (pintype "bidirectional"))
      (node (ref "J2") (pin "P$31") (pinfunction "P$31_P$31") (pintype "bidirectional"))
      (node (ref "J2") (pin "P$37") (pinfunction "P$37_P$37") (pintype "bidirectional"))
      (node (ref "J2") (pin "P$40") (pinfunction "P$40_P$40") (pintype "bidirectional"))
      (node (ref "J2") (pin "P$43") (pinfunction "P$43_P$43") (pintype "bidirectional"))
      (node (ref "J2") (pin "P$46") (pinfunction "P$46_P$46") (pintype "bidirectional"))
      (node (ref "J2") (pin "P$49") (pinfunction "P$49_P$49") (pintype "bidirectional"))
      (node (ref "J2") (pin "P$52") (pinfunction "P$52_P$52") (pintype "bidirectional"))
      (node (ref "J2") (pin "P$55") (pinfunction "P$55_P$55") (pintype "bidirectional"))
      (node (ref "J2") (pin "P$58") (pinfunction "P$58_P$58") (pintype "bidirectional"))
      (node (ref "J2") (pin "P$6") (pinfunction "P$6_P$6") (pintype "bidirectional"))
      (node (ref "J3") (pin "4") (pinfunction "4_4") (pintype "passive"))
      (node (ref "J3") (pin "SH1") (pinfunction "SHIELD_SH1") (pintype "power_in"))
      (node (ref "J3") (pin "SH2") (pinfunction "SHIELD_SH2") (pintype "power_in"))
      (node (ref "J4") (pin "4") (pinfunction "4_4") (pintype "passive"))
      (node (ref "J4") (pin "SH1") (pinfunction "SHIELD_SH1") (pintype "power_in"))
      (node (ref "J4") (pin "SH2") (pinfunction "SHIELD_SH2") (pintype "power_in"))
      (node (ref "J5") (pin "2") (pinfunction "S_2") (pintype "passive"))
      (node (ref "J6") (pin "4") (pinfunction "4_4") (pintype "passive"))
      (node (ref "J6") (pin "SH1") (pinfunction "SHIELD_SH1") (pintype "power_in"))
      (node (ref "J6") (pin "SH2") (pinfunction "SHIELD_SH2") (pintype "power_in"))
      (node (ref "J7") (pin "4") (pinfunction "4_4") (pintype "passive"))
      (node (ref "J7") (pin "SH1") (pinfunction "SHIELD_SH1") (pintype "power_in"))
      (node (ref "J7") (pin "SH2") (pinfunction "SHIELD_SH2") (pintype "power_in"))
      (node (ref "J8") (pin "6") (pinfunction "6_6") (pintype "passive"))
      (node (ref "J8") (pin "S1") (pinfunction "SHIELD_S1") (pintype "passive"))
      (node (ref "J8") (pin "S2") (pinfunction "SHIELD_S2") (pintype "passive"))
      (node (ref "PCB1") (pin "G$1") (pinfunction "P$1_G$1") (pintype "bidirectional"))
      (node (ref "PCB1") (pin "G$2") (pinfunction "P$2_G$2") (pintype "bidirectional"))
      (node (ref "PCB1") (pin "G$3") (pinfunction "P$3_G$3") (pintype "bidirectional"))
      (node (ref "PCB1") (pin "G$4") (pinfunction "P$4_G$4") (pintype "bidirectional"))
      (node (ref "PS1") (pin "2") (pinfunction "GND_2") (pintype "power_in"))
      (node (ref "S1") (pin "GND") (pinfunction "GND_GND") (pintype "bidirectional"))
      (node (ref "S2") (pin "B2") (pinfunction "2_B2") (pintype "passive"))
      (node (ref "U$1") (pin "GND") (pinfunction "GND_GND") (pintype "power_in"))
      (node (ref "U$2") (pin "2") (pinfunction "VIN-_2") (pintype "bidirectional"))
      (node (ref "U$2") (pin "5") (pinfunction "VOUT-_5") (pintype "bidirectional"))
      (node (ref "U1") (pin "1") (pinfunction "GND_1") (pintype "power_in"))
      (node (ref "U1") (pin "5") (pinfunction "SDO_5") (pintype "bidirectional"))
      (node (ref "U1") (pin "7") (pinfunction "GND_7") (pintype "power_in"))
      (node (ref "U2") (pin "6") (pinfunction "VSS_6") (pintype "power_in"))
      (node (ref "U4") (pin "5") (pinfunction "A0_5") (pintype "input"))
      (node (ref "U4") (pin "6") (pinfunction "VSS_6") (pintype "power_in"))
      (node (ref "U4") (pin "7") (pinfunction "A1_7") (pintype "input"))
      (node (ref "U5") (pin "11") (pinfunction "GND_11") (pintype "power_in"))
      (node (ref "U5") (pin "4") (pinfunction "A1_4") (pintype "input"))
      (node (ref "U5") (pin "5") (pinfunction "A0_5") (pintype "input"))
      (node (ref "U5") (pin "6") (pinfunction "GND_6") (pintype "power_in"))
      (node (ref "U6") (pin "P$2") (pinfunction "GND_P$2") (pintype "bidirectional"))
      (node (ref "U7") (pin "2") (pinfunction "GND_2") (pintype "passive"))
      (node (ref "U9") (pin "7") (pinfunction "GND_7") (pintype "bidirectional"))
    )
    (net (code "36") (name "GPIO-A") (class "Default")
      (node (ref "J1") (pin "P$23") (pinfunction "P$23_P$23") (pintype "bidirectional"))
    )
    (net (code "37") (name "GPIO-B") (class "Default")
      (node (ref "J1") (pin "P$24") (pinfunction "P$24_P$24") (pintype "bidirectional"))
    )
    (net (code "38") (name "GPIO-C") (class "Default")
      (node (ref "J1") (pin "P$25") (pinfunction "P$25_P$25") (pintype "bidirectional"))
    )
    (net (code "39") (name "GPIO-D") (class "Default")
      (node (ref "J1") (pin "P$26") (pinfunction "P$26_P$26") (pintype "bidirectional"))
    )
    (net (code "40") (name "GPIO-E") (class "Default")
      (node (ref "J1") (pin "P$27") (pinfunction "P$27_P$27") (pintype "bidirectional"))
    )
    (net (code "41") (name "GPIO-F") (class "Default")
      (node (ref "J1") (pin "P$28") (pinfunction "P$28_P$28") (pintype "bidirectional"))
    )
    (net (code "42") (name "GPIO-G") (class "Default")
      (node (ref "J1") (pin "P$29") (pinfunction "P$29_P$29") (pintype "bidirectional"))
      (node (ref "R10") (pin "1") (pinfunction "1_1") (pintype "passive"))
      (node (ref "S1") (pin "B") (pinfunction "RIGHT_B") (pintype "bidirectional"))
    )
    (net (code "43") (name "GPIO-H") (class "Default")
      (node (ref "J1") (pin "P$30") (pinfunction "P$30_P$30") (pintype "bidirectional"))
    )
    (net (code "44") (name "GPIO-I") (class "Default")
      (node (ref "J1") (pin "P$31") (pinfunction "P$31_P$31") (pintype "bidirectional"))
      (node (ref "R9") (pin "1") (pinfunction "1_1") (pintype "passive"))
      (node (ref "S1") (pin "C") (pinfunction "LEFT_C") (pintype "bidirectional"))
    )
    (net (code "45") (name "GPIO-J") (class "Default")
      (node (ref "J1") (pin "P$32") (pinfunction "P$32_P$32") (pintype "bidirectional"))
      (node (ref "R4") (pin "1") (pinfunction "1_1") (pintype "passive"))
      (node (ref "S1") (pin "D") (pinfunction "DOWN_D") (pintype "bidirectional"))
    )
    (net (code "46") (name "GPIO-K") (class "Default")
      (node (ref "J1") (pin "P$33") (pinfunction "P$33_P$33") (pintype "bidirectional"))
      (node (ref "R3") (pin "1") (pinfunction "1_1") (pintype "passive"))
      (node (ref "S1") (pin "A") (pinfunction "UP_A") (pintype "bidirectional"))
    )
    (net (code "47") (name "GPIO-L") (class "Default")
      (node (ref "J1") (pin "P$34") (pinfunction "P$34_P$34") (pintype "bidirectional"))
      (node (ref "R11") (pin "1") (pinfunction "1_1") (pintype "passive"))
      (node (ref "S1") (pin "CTR") (pinfunction "CENT_CTR") (pintype "bidirectional"))
    )
    (net (code "48") (name "HSIC_DATA") (class "Default")
      (node (ref "J2") (pin "P$59") (pinfunction "P$59_P$59") (pintype "bidirectional"))
    )
    (net (code "49") (name "HSIC_STR") (class "Default")
      (node (ref "J2") (pin "P$57") (pinfunction "P$57_P$57") (pintype "bidirectional"))
    )
    (net (code "50") (name "I2C0_SCL") (class "Default")
      (node (ref "J1") (pin "P$15") (pinfunction "P$15_P$15") (pintype "bidirectional"))
    )
    (net (code "51") (name "I2C0_SDA") (class "Default")
      (node (ref "J1") (pin "P$17") (pinfunction "P$17_P$17") (pintype "bidirectional"))
    )
    (net (code "52") (name "I2C1_SCL") (class "Default")
      (node (ref "J1") (pin "P$19") (pinfunction "P$19_P$19") (pintype "bidirectional"))
      (node (ref "R1") (pin "1") (pinfunction "1_1") (pintype "passive"))
      (node (ref "U6") (pin "P$4") (pinfunction "A2_P$4") (pintype "bidirectional"))
    )
    (net (code "53") (name "I2C1_SDA") (class "Default")
      (node (ref "J1") (pin "P$21") (pinfunction "P$21_P$21") (pintype "bidirectional"))
      (node (ref "R2") (pin "1") (pinfunction "1_1") (pintype "passive"))
      (node (ref "U6") (pin "P$5") (pinfunction "A1_P$5") (pintype "bidirectional"))
    )
    (net (code "54") (name "I2C2_SCL") (class "Default")
      (node (ref "J2") (pin "P$32") (pinfunction "P$32_P$32") (pintype "bidirectional"))
    )
    (net (code "55") (name "I2C2_SDA") (class "Default")
      (node (ref "J2") (pin "P$34") (pinfunction "P$34_P$34") (pintype "bidirectional"))
    )
    (net (code "56") (name "I2C3_SCL") (class "Default")
      (node (ref "J2") (pin "P$36") (pinfunction "P$36_P$36") (pintype "bidirectional"))
    )
    (net (code "57") (name "I2C3_SDA") (class "Default")
      (node (ref "J2") (pin "P$38") (pinfunction "P$38_P$38") (pintype "bidirectional"))
    )
    (net (code "58") (name "MISO") (class "Default")
      (node (ref "J8") (pin "4") (pinfunction "4_4") (pintype "passive"))
      (node (ref "U9") (pin "11") (pinfunction "B3_11") (pintype "bidirectional"))
    )
    (net (code "59") (name "MOSI") (class "Default")
      (node (ref "J8") (pin "5") (pinfunction "5_5") (pintype "passive"))
      (node (ref "U9") (pin "10") (pinfunction "B4_10") (pintype "bidirectional"))
    )
    (net (code "60") (name "Net-(D1-PadA)") (class "Default")
      (node (ref "D1") (pin "A") (pinfunction "A_A") (pintype "passive"))
      (node (ref "R15") (pin "1") (pinfunction "1_1") (pintype "passive"))
    )
    (net (code "61") (name "Net-(D2-PadA)") (class "Default")
      (node (ref "D2") (pin "A") (pinfunction "A_A") (pintype "passive"))
      (node (ref "R16") (pin "1") (pinfunction "1_1") (pintype "passive"))
    )
    (net (code "62") (name "Net-(D3-PadA)") (class "Default")
      (node (ref "D3") (pin "A") (pinfunction "A_A") (pintype "passive"))
      (node (ref "R18") (pin "1") (pinfunction "1_1") (pintype "passive"))
    )
    (net (code "63") (name "Net-(D4-PadA)") (class "Default")
      (node (ref "D4") (pin "A") (pinfunction "A_A") (pintype "passive"))
      (node (ref "R17") (pin "1") (pinfunction "1_1") (pintype "passive"))
    )
    (net (code "64") (name "Net-(D5-PadA)") (class "Default")
      (node (ref "D5") (pin "A") (pinfunction "A_A") (pintype "passive"))
      (node (ref "R7") (pin "1") (pinfunction "1_1") (pintype "passive"))
    )
    (net (code "65") (name "Net-(D6-B_A)") (class "Default")
      (node (ref "D6") (pin "6") (pinfunction "B_A_6") (pintype "passive"))
      (node (ref "R19") (pin "1") (pinfunction "1_1") (pintype "passive"))
    )
    (net (code "66") (name "Net-(D6-B_C)") (class "Default")
      (node (ref "D6") (pin "1") (pinfunction "B_C_1") (pintype "passive"))
      (node (ref "U4") (pin "3") (pinfunction "LED2_3") (pintype "output"))
    )
    (net (code "67") (name "Net-(D6-G_A)") (class "Default")
      (node (ref "D6") (pin "5") (pinfunction "G_A_5") (pintype "passive"))
      (node (ref "R20") (pin "1") (pinfunction "1_1") (pintype "passive"))
    )
    (net (code "68") (name "Net-(D6-G_C)") (class "Default")
      (node (ref "D6") (pin "2") (pinfunction "G_C_2") (pintype "passive"))
      (node (ref "U4") (pin "2") (pinfunction "LED1_2") (pintype "output"))
    )
    (net (code "69") (name "Net-(D6-R_A)") (class "Default")
      (node (ref "D6") (pin "4") (pinfunction "R_A_4") (pintype "passive"))
      (node (ref "R21") (pin "1") (pinfunction "1_1") (pintype "passive"))
    )
    (net (code "70") (name "Net-(D6-R_C)") (class "Default")
      (node (ref "D6") (pin "3") (pinfunction "R_C_3") (pintype "passive"))
      (node (ref "U4") (pin "1") (pinfunction "LED0_1") (pintype "output"))
    )
    (net (code "71") (name "Net-(D7-PadA)") (class "Default")
      (node (ref "D7") (pin "A") (pinfunction "A_A") (pintype "passive"))
      (node (ref "R6") (pin "2") (pinfunction "2_2") (pintype "passive"))
    )
    (net (code "72") (name "Net-(D8-PadA)") (class "Default")
      (node (ref "D8") (pin "A") (pinfunction "A_A") (pintype "passive"))
      (node (ref "R8") (pin "1") (pinfunction "1_1") (pintype "passive"))
    )
    (net (code "73") (name "Net-(D10-PadA)") (class "Default")
      (node (ref "D10") (pin "A") (pinfunction "A_A") (pintype "passive"))
      (node (ref "R12") (pin "1") (pinfunction "1_1") (pintype "passive"))
    )
    (net (code "74") (name "Net-(PS1-+VIN)") (class "Default")
      (node (ref "F1") (pin "1") (pinfunction "1_1") (pintype "passive"))
      (node (ref "PS1") (pin "1") (pinfunction "+VIN_1") (pintype "input"))
      (node (ref "TP2") (pin "P$1") (pinfunction "1_P$1") (pintype "bidirectional"))
      (node (ref "U$2") (pin "1") (pinfunction "VIN_1") (pintype "bidirectional"))
      (node (ref "U$2") (pin "6") (pinfunction "EN_6") (pintype "bidirectional"))
    )
    (net (code "75") (name "Net-(U2-LED0)") (class "Default")
      (node (ref "D1") (pin "C") (pinfunction "C_C") (pintype "passive"))
      (node (ref "U2") (pin "1") (pinfunction "LED0_1") (pintype "output"))
    )
    (net (code "76") (name "Net-(U2-LED1)") (class "Default")
      (node (ref "D2") (pin "C") (pinfunction "C_C") (pintype "passive"))
      (node (ref "U2") (pin "2") (pinfunction "LED1_2") (pintype "output"))
    )
    (net (code "77") (name "Net-(U2-LED2)") (class "Default")
      (node (ref "D4") (pin "C") (pinfunction "C_C") (pintype "passive"))
      (node (ref "U2") (pin "3") (pinfunction "LED2_3") (pintype "output"))
    )
    (net (code "78") (name "Net-(U2-LED3)") (class "Default")
      (node (ref "D3") (pin "C") (pinfunction "C_C") (pintype "passive"))
      (node (ref "U2") (pin "4") (pinfunction "LED3_4") (pintype "output"))
    )
    (net (code "79") (name "Net-(U3-B1)") (class "Default")
      (node (ref "J3") (pin "2") (pinfunction "2_2") (pintype "passive"))
      (node (ref "U3") (pin "P$8") (pinfunction "B1_P$8") (pintype "bidirectional"))
    )
    (net (code "80") (name "Net-(U3-B2)") (class "Default")
      (node (ref "J3") (pin "3") (pinfunction "3_3") (pintype "passive"))
      (node (ref "U3") (pin "P$1") (pinfunction "B2_P$1") (pintype "bidirectional"))
    )
    (net (code "81") (name "Net-(U5-ALERT)") (class "Default")
      (node (ref "D7") (pin "C") (pinfunction "C_C") (pintype "passive"))
      (node (ref "R5") (pin "1") (pinfunction "1_1") (pintype "passive"))
      (node (ref "U5") (pin "7") (pinfunction "ALERT_7") (pintype "output"))
    )
    (net (code "82") (name "Net-(U7-NR{slash}FB)") (class "Default")
      (node (ref "C19") (pin "1") (pinfunction "1_1") (pintype "passive"))
      (node (ref "U7") (pin "4") (pinfunction "NR/FB_4") (pintype "passive"))
    )
    (net (code "83") (name "Net-(U8-B1)") (class "Default")
      (node (ref "J4") (pin "2") (pinfunction "2_2") (pintype "passive"))
      (node (ref "U8") (pin "P$8") (pinfunction "B1_P$8") (pintype "bidirectional"))
    )
    (net (code "84") (name "Net-(U8-B2)") (class "Default")
      (node (ref "J4") (pin "3") (pinfunction "3_3") (pintype "passive"))
      (node (ref "U8") (pin "P$1") (pinfunction "B2_P$1") (pintype "bidirectional"))
    )
    (net (code "85") (name "Net-(X1-ANT)") (class "Default")
      (node (ref "ANT1") (pin "SIG") (pinfunction "SIG_SIG") (pintype "bidirectional"))
      (node (ref "X1") (pin "P") (pinfunction "ANT_P") (pintype "bidirectional"))
    )
    (net (code "86") (name "Net-(X1-GND1)") (class "Default")
      (node (ref "ANT1") (pin "GND1") (pinfunction "GND1_GND1") (pintype "bidirectional"))
      (node (ref "ANT1") (pin "GND2") (pinfunction "GND2_GND2") (pintype "bidirectional"))
      (node (ref "X1") (pin "GND@1") (pinfunction "GND4_GND@1") (pintype "power_in"))
      (node (ref "X1") (pin "GND@2") (pinfunction "GND3_GND@2") (pintype "power_in"))
      (node (ref "X1") (pin "GND@3") (pinfunction "GND2_GND@3") (pintype "power_in"))
      (node (ref "X1") (pin "GND@4") (pinfunction "GND1_GND@4") (pintype "power_in"))
    )
    (net (code "87") (name "Net-(X2-ANT)") (class "Default")
      (node (ref "ANT2") (pin "SIG") (pinfunction "SIG_SIG") (pintype "bidirectional"))
      (node (ref "X2") (pin "P") (pinfunction "ANT_P") (pintype "bidirectional"))
    )
    (net (code "88") (name "Net-(X2-GND1)") (class "Default")
      (node (ref "ANT2") (pin "GND1") (pinfunction "GND1_GND1") (pintype "bidirectional"))
      (node (ref "ANT2") (pin "GND2") (pinfunction "GND2_GND2") (pintype "bidirectional"))
      (node (ref "X2") (pin "GND@1") (pinfunction "GND4_GND@1") (pintype "power_in"))
      (node (ref "X2") (pin "GND@2") (pinfunction "GND3_GND@2") (pintype "power_in"))
      (node (ref "X2") (pin "GND@3") (pinfunction "GND2_GND@3") (pintype "power_in"))
      (node (ref "X2") (pin "GND@4") (pinfunction "GND1_GND@4") (pintype "power_in"))
    )
    (net (code "89") (name "PCM_CLK") (class "Default")
      (node (ref "J1") (pin "P$18") (pinfunction "P$18_P$18") (pintype "bidirectional"))
    )
    (net (code "90") (name "PCM_DI") (class "Default")
      (node (ref "J1") (pin "P$22") (pinfunction "P$22_P$22") (pintype "bidirectional"))
    )
    (net (code "91") (name "PCM_DO") (class "Default")
      (node (ref "J1") (pin "P$20") (pinfunction "P$20_P$20") (pintype "bidirectional"))
    )
    (net (code "92") (name "PCM_FS") (class "Default")
      (node (ref "J1") (pin "P$16") (pinfunction "P$16_P$16") (pintype "bidirectional"))
    )
    (net (code "93") (name "PWR_BTN_N") (class "Default")
      (node (ref "J1") (pin "P$4") (pinfunction "P$4_P$4") (pintype "bidirectional"))
    )
    (net (code "94") (name "RESERVED") (class "Default")
      (node (ref "J2") (pin "P$60") (pinfunction "P$60_P$60") (pintype "bidirectional"))
    )
    (net (code "95") (name "RST_BTN_N") (class "Default")
      (node (ref "J1") (pin "P$6") (pinfunction "P$6_P$6") (pintype "bidirectional"))
      (node (ref "S2") (pin "A2") (pinfunction "1_A2") (pintype "passive"))
    )
    (net (code "96") (name "SCLK") (class "Default")
      (node (ref "J8") (pin "2") (pinfunction "2_2") (pintype "passive"))
      (node (ref "U9") (pin "13") (pinfunction "B1_13") (pintype "bidirectional"))
    )
    (net (code "97") (name "SCL_3V3") (class "Default")
      (node (ref "J6") (pin "2") (pinfunction "2_2") (pintype "passive"))
      (node (ref "J7") (pin "2") (pinfunction "2_2") (pintype "passive"))
      (node (ref "R13") (pin "1") (pinfunction "1_1") (pintype "passive"))
      (node (ref "TP7") (pin "P$1") (pinfunction "1_P$1") (pintype "bidirectional"))
      (node (ref "U$1") (pin "SCL") (pinfunction "SCL_SCL") (pintype "input"))
      (node (ref "U1") (pin "4") (pinfunction "SCLK_4") (pintype "bidirectional"))
      (node (ref "U2") (pin "8") (pinfunction "SCL_8") (pintype "input"))
      (node (ref "U4") (pin "8") (pinfunction "SCL_8") (pintype "input"))
      (node (ref "U5") (pin "9") (pinfunction "SCL_9") (pintype "input"))
      (node (ref "U6") (pin "P$1") (pinfunction "B2_P$1") (pintype "bidirectional"))
    )
    (net (code "98") (name "SDA_3V3") (class "Default")
      (node (ref "J6") (pin "3") (pinfunction "3_3") (pintype "passive"))
      (node (ref "J7") (pin "3") (pinfunction "3_3") (pintype "passive"))
      (node (ref "R14") (pin "1") (pinfunction "1_1") (pintype "passive"))
      (node (ref "TP6") (pin "P$1") (pinfunction "1_P$1") (pintype "bidirectional"))
      (node (ref "U$1") (pin "SDA") (pinfunction "SDA_SDA") (pintype "bidirectional"))
      (node (ref "U1") (pin "3") (pinfunction "SDI_3") (pintype "bidirectional"))
      (node (ref "U2") (pin "9") (pinfunction "SDA_9") (pintype "bidirectional"))
      (node (ref "U4") (pin "9") (pinfunction "SDA_9") (pintype "bidirectional"))
      (node (ref "U5") (pin "8") (pinfunction "SDA_8") (pintype "bidirectional"))
      (node (ref "U6") (pin "P$8") (pinfunction "B1_P$8") (pintype "bidirectional"))
    )
    (net (code "99") (name "SD_CMD{slash}SPI1_DIN") (class "Default")
      (node (ref "J2") (pin "P$11") (pinfunction "P$11_P$11") (pintype "bidirectional"))
    )
    (net (code "100") (name "SD_DAT0{slash}SPI1_DOUT") (class "Default")
      (node (ref "J2") (pin "P$1") (pinfunction "P$1_P$1") (pintype "bidirectional"))
    )
    (net (code "101") (name "SD_DAT1") (class "Default")
      (node (ref "J2") (pin "P$3") (pinfunction "P$3_P$3") (pintype "bidirectional"))
    )
    (net (code "102") (name "SD_DAT2") (class "Default")
      (node (ref "J2") (pin "P$5") (pinfunction "P$5_P$5") (pintype "bidirectional"))
    )
    (net (code "103") (name "SD_DAT3{slash}SPI1_CS") (class "Default")
      (node (ref "J2") (pin "P$7") (pinfunction "P$7_P$7") (pintype "bidirectional"))
    )
    (net (code "104") (name "SD_SCLK{slash}SPI1_SCLK") (class "Default")
      (node (ref "J2") (pin "P$9") (pinfunction "P$9_P$9") (pintype "bidirectional"))
    )
    (net (code "105") (name "SPI0_CS") (class "Default")
      (node (ref "J1") (pin "P$12") (pinfunction "P$12_P$12") (pintype "bidirectional"))
      (node (ref "U9") (pin "3") (pinfunction "A2_3") (pintype "bidirectional"))
    )
    (net (code "106") (name "SPI0_DIN") (class "Default")
      (node (ref "J1") (pin "P$10") (pinfunction "P$10_P$10") (pintype "bidirectional"))
      (node (ref "U9") (pin "4") (pinfunction "A3_4") (pintype "bidirectional"))
    )
    (net (code "107") (name "SPI0_DOUT") (class "Default")
      (node (ref "J1") (pin "P$14") (pinfunction "P$14_P$14") (pintype "bidirectional"))
      (node (ref "U9") (pin "2") (pinfunction "A1_2") (pintype "bidirectional"))
    )
    (net (code "108") (name "SPI0_SCLK") (class "Default")
      (node (ref "J1") (pin "P$8") (pinfunction "P$8_P$8") (pintype "bidirectional"))
      (node (ref "U9") (pin "5") (pinfunction "A4_5") (pintype "bidirectional"))
    )
    (net (code "109") (name "SYS_DCIN") (class "Default")
      (node (ref "C16") (pin "1") (pinfunction "1_1") (pintype "passive"))
      (node (ref "C17") (pin "1") (pinfunction "1_1") (pintype "passive"))
      (node (ref "C18") (pin "1") (pinfunction "1_1") (pintype "passive"))
      (node (ref "J1") (pin "P$36") (pinfunction "P$36_P$36") (pintype "bidirectional"))
      (node (ref "J1") (pin "P$38") (pinfunction "P$38_P$38") (pintype "bidirectional"))
      (node (ref "R8") (pin "2") (pinfunction "2_2") (pintype "passive"))
      (node (ref "U5") (pin "14") (pinfunction "IN-_14") (pintype "input"))
      (node (ref "U5") (pin "15") (pinfunction "IN-_15") (pintype "input"))
      (node (ref "U5") (pin "16") (pinfunction "IN-_16") (pintype "input"))
    )
    (net (code "110") (name "UART0_CTS") (class "Default")
      (node (ref "J1") (pin "P$3") (pinfunction "P$3_P$3") (pintype "bidirectional"))
    )
    (net (code "111") (name "UART0_RTS") (class "Default")
      (node (ref "J1") (pin "P$9") (pinfunction "P$9_P$9") (pintype "bidirectional"))
    )
    (net (code "112") (name "UART0_RXD") (class "Default")
      (node (ref "J1") (pin "P$7") (pinfunction "P$7_P$7") (pintype "bidirectional"))
      (node (ref "U3") (pin "P$4") (pinfunction "A2_P$4") (pintype "bidirectional"))
    )
    (net (code "113") (name "UART0_TXD") (class "Default")
      (node (ref "J1") (pin "P$5") (pinfunction "P$5_P$5") (pintype "bidirectional"))
      (node (ref "U3") (pin "P$5") (pinfunction "A1_P$5") (pintype "bidirectional"))
    )
    (net (code "114") (name "UART1_RXD") (class "Default")
      (node (ref "J1") (pin "P$13") (pinfunction "P$13_P$13") (pintype "bidirectional"))
      (node (ref "U8") (pin "P$4") (pinfunction "A2_P$4") (pintype "bidirectional"))
    )
    (net (code "115") (name "UART1_TXD") (class "Default")
      (node (ref "J1") (pin "P$11") (pinfunction "P$11_P$11") (pintype "bidirectional"))
      (node (ref "U8") (pin "P$5") (pinfunction "A1_P$5") (pintype "bidirectional"))
    )
    (net (code "116") (name "USB_D+") (class "Default")
      (node (ref "J2") (pin "P$51") (pinfunction "P$51_P$51") (pintype "bidirectional"))
    )
    (net (code "117") (name "USB_D-") (class "Default")
      (node (ref "J2") (pin "P$53") (pinfunction "P$53_P$53") (pintype "bidirectional"))
    )
    (net (code "118") (name "unconnected-(U$2-TRIM-Pad4)") (class "Default")
      (node (ref "U$2") (pin "4") (pinfunction "TRIM_4") (pintype "bidirectional"))
    )
    (net (code "119") (name "unconnected-(U3-GND-PadP$2)") (class "Default")
      (node (ref "U3") (pin "P$2") (pinfunction "GND_P$2") (pintype "bidirectional"))
    )
    (net (code "120") (name "unconnected-(U4-LED3-Pad4)") (class "Default")
      (node (ref "U4") (pin "4") (pinfunction "LED3_4") (pintype "output"))
    )
    (net (code "121") (name "unconnected-(U5-NC-Pad13)") (class "Default")
      (node (ref "U5") (pin "13") (pinfunction "NC_13") (pintype "no_connect"))
    )
    (net (code "122") (name "unconnected-(U8-GND-PadP$2)") (class "Default")
      (node (ref "U8") (pin "P$2") (pinfunction "GND_P$2") (pintype "bidirectional"))
    )
  )
)
